# Zynq_config_JTAG_Debug.net
KiCad netlist of a schematic drawn in Altium Designer
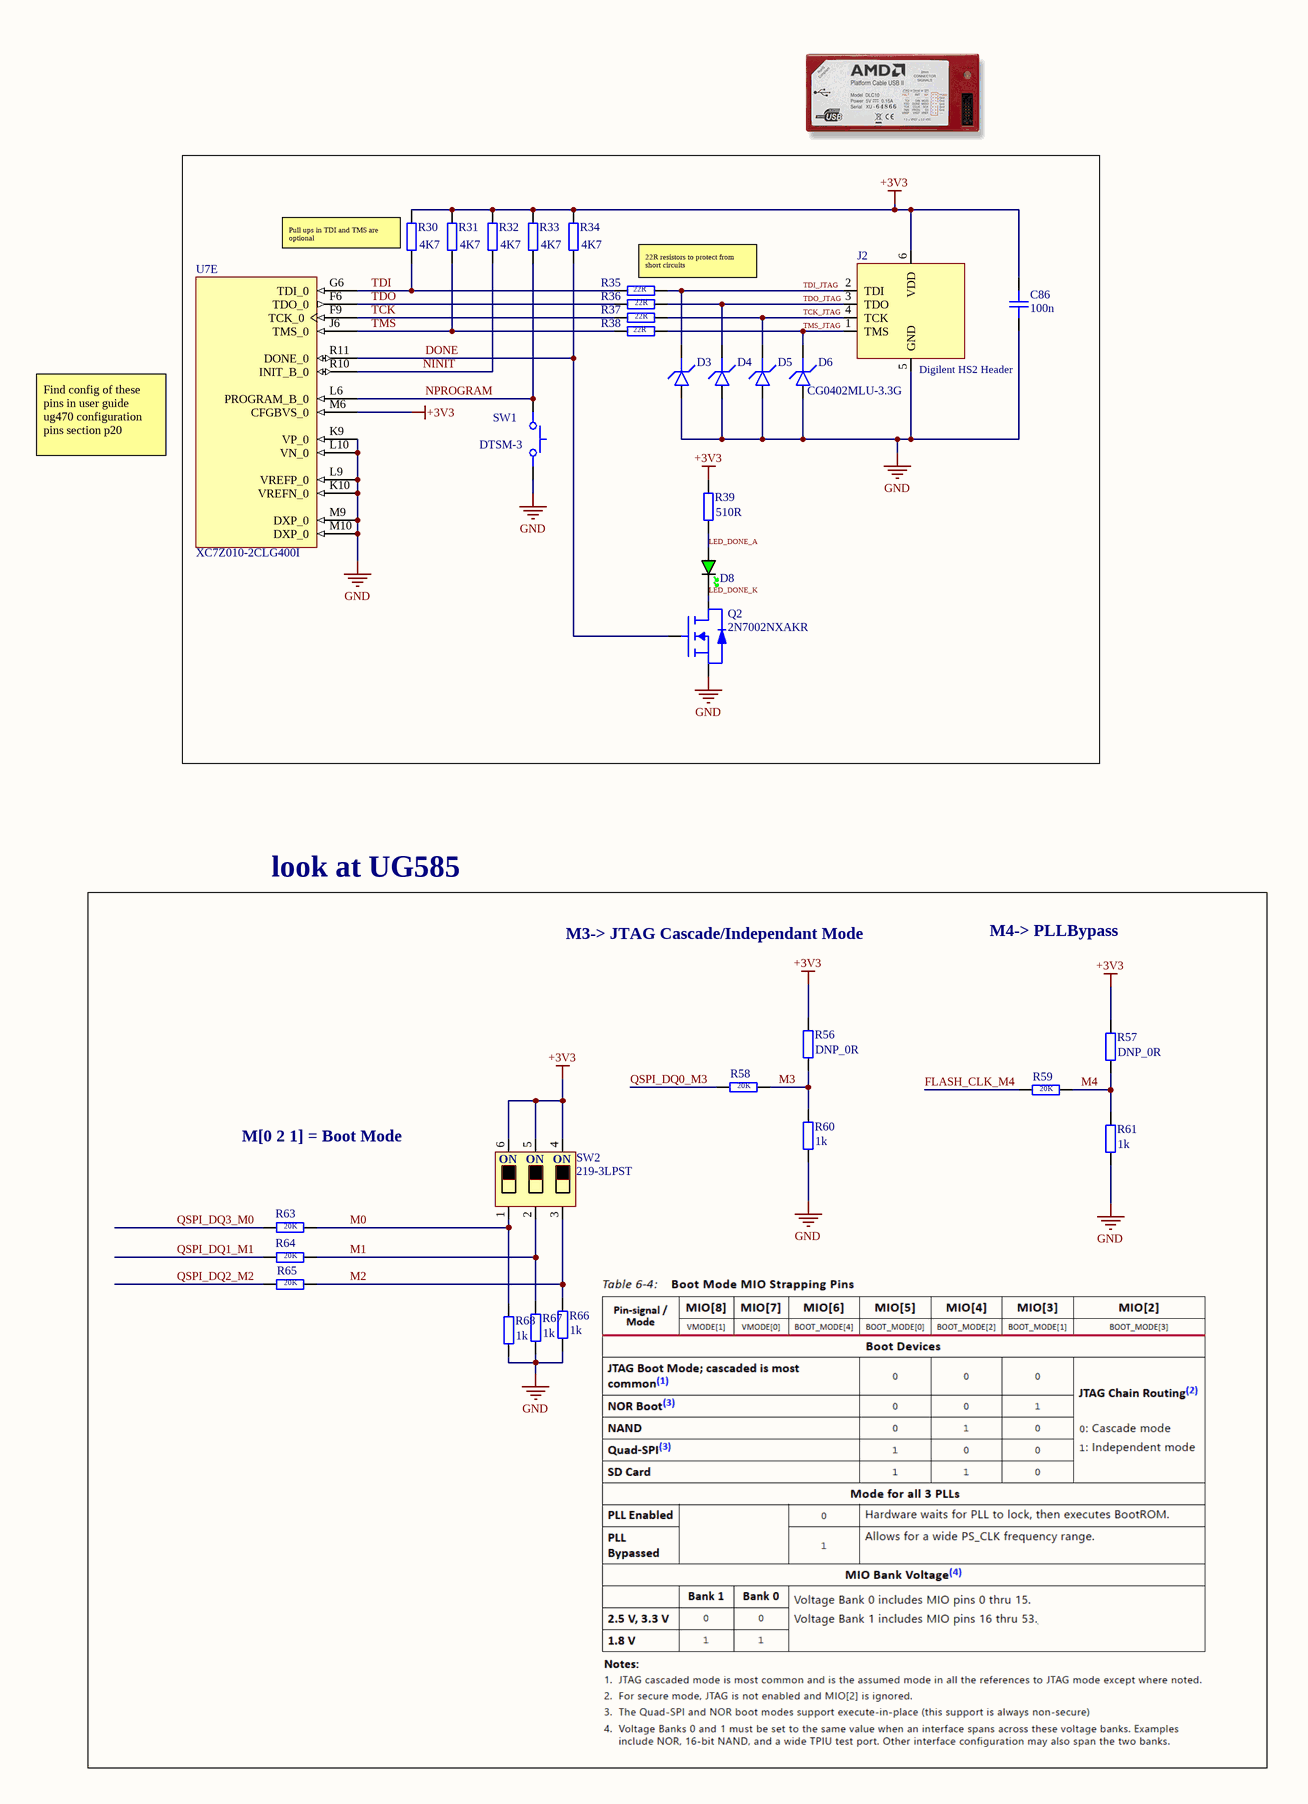
[diagram p0: Zynq config, JTAG, Debug.SchDoc, left]
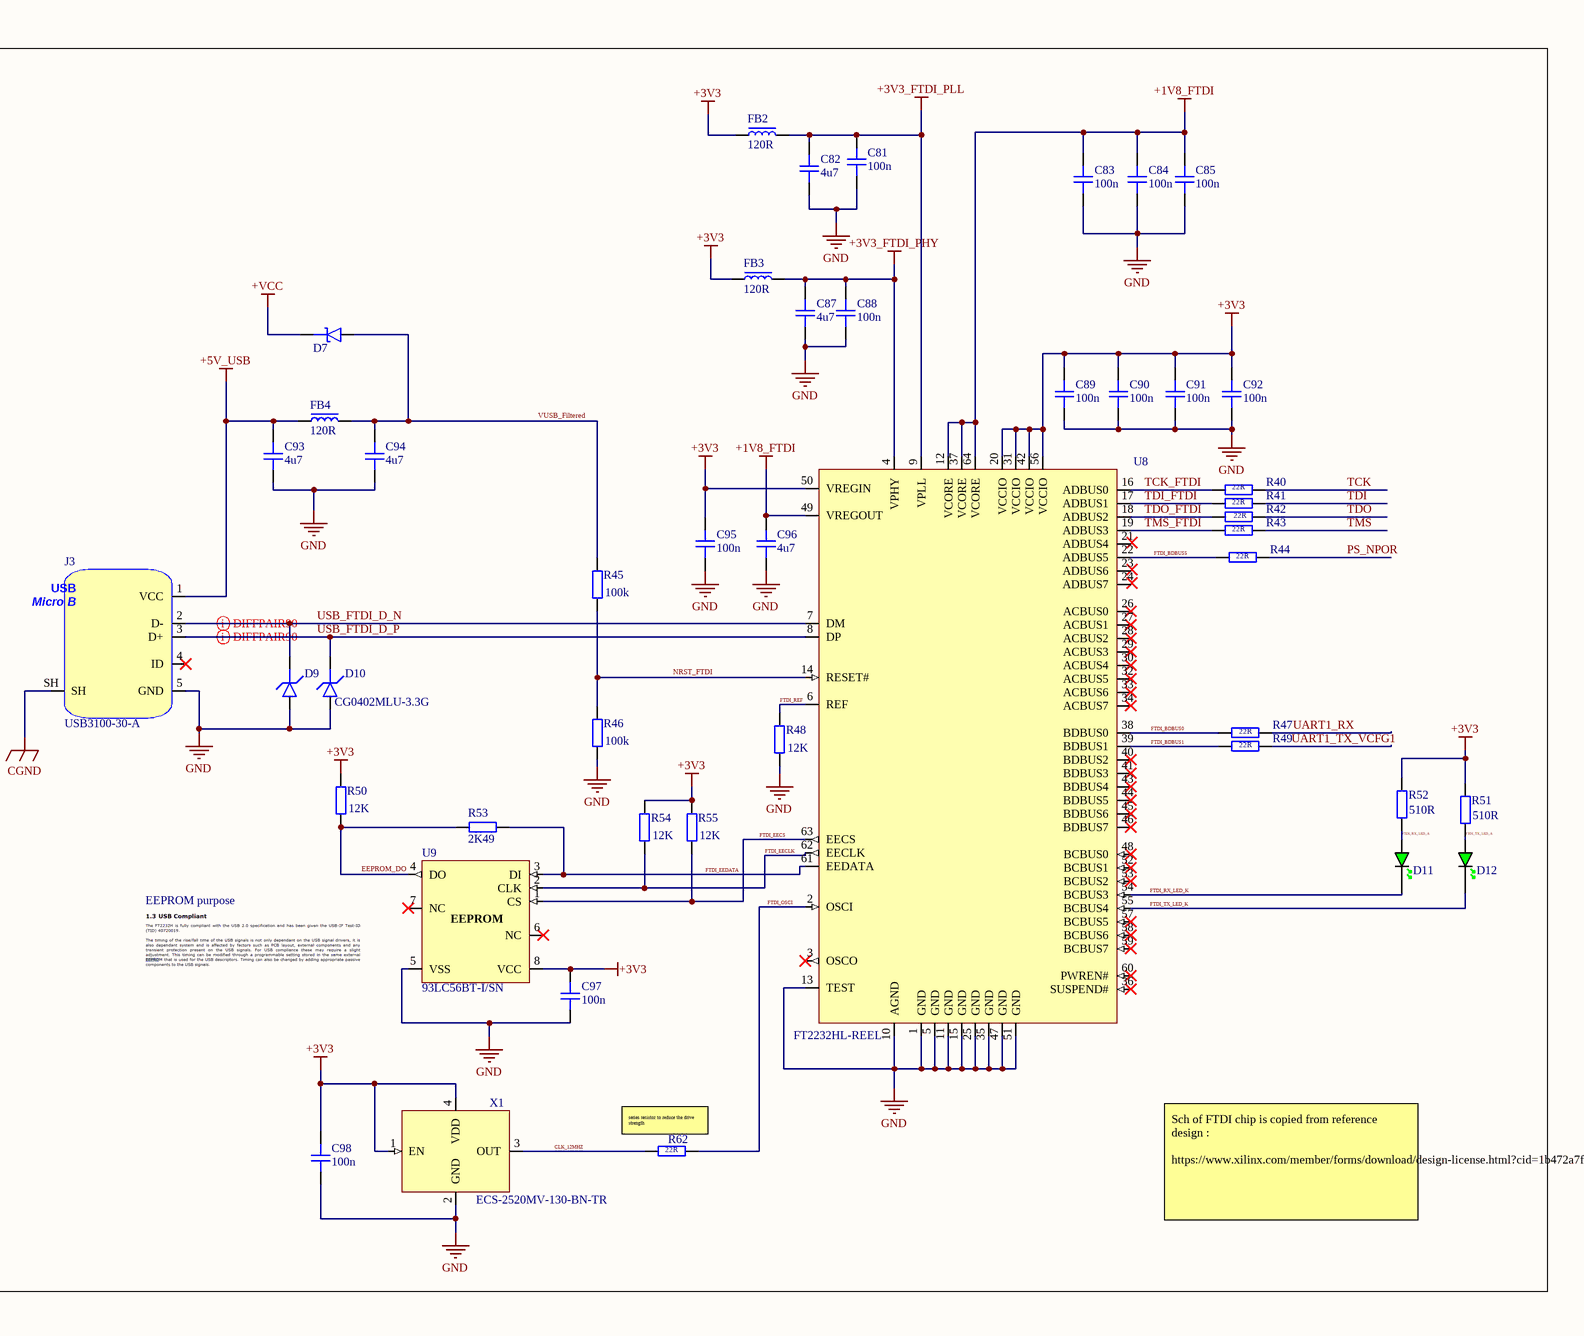
[diagram p1: Zynq config, JTAG, Debug.SchDoc, right]

(export (version "E")
  (design (tool "Eeschema 10.0.6"))
  (components
    (comp (ref "C81")
      (value "100n")
      (footprint "CAP_0402")
      (description "Capacitor SMD 0402")
      (libsource (lib "Schematic-Lib-PhilsLab") (part "CAP_0402"))
    )
    (comp (ref "C82")
      (value "4u7")
      (footprint "CAP_0402")
      (description "Capacitor SMD 0402")
      (libsource (lib "Schematic-Lib-PhilsLab") (part "CAP_0402"))
    )
    (comp (ref "C83")
      (value "100n")
      (footprint "CAP_0402")
      (description "Capacitor SMD 0402")
      (libsource (lib "Schematic-Lib-PhilsLab") (part "CAP_0402"))
    )
    (comp (ref "C84")
      (value "100n")
      (footprint "CAP_0402")
      (description "Capacitor SMD 0402")
      (libsource (lib "Schematic-Lib-PhilsLab") (part "CAP_0402"))
    )
    (comp (ref "C85")
      (value "100n")
      (footprint "CAP_0402")
      (description "Capacitor SMD 0402")
      (libsource (lib "Schematic-Lib-PhilsLab") (part "CAP_0402"))
    )
    (comp (ref "C86")
      (value "100n")
      (footprint "CAP_0402")
      (description "Capacitor SMD 0402")
      (libsource (lib "Schematic-Lib-PhilsLab") (part "CAP_0402"))
    )
    (comp (ref "C87")
      (value "4u7")
      (footprint "CAP_0402")
      (description "Capacitor SMD 0402")
      (libsource (lib "Schematic-Lib-PhilsLab") (part "CAP_0402"))
    )
    (comp (ref "C88")
      (value "100n")
      (footprint "CAP_0402")
      (description "Capacitor SMD 0402")
      (libsource (lib "Schematic-Lib-PhilsLab") (part "CAP_0402"))
    )
    (comp (ref "C89")
      (value "100n")
      (footprint "CAP_0402")
      (description "Capacitor SMD 0402")
      (libsource (lib "Schematic-Lib-PhilsLab") (part "CAP_0402"))
    )
    (comp (ref "C90")
      (value "100n")
      (footprint "CAP_0402")
      (description "Capacitor SMD 0402")
      (libsource (lib "Schematic-Lib-PhilsLab") (part "CAP_0402"))
    )
    (comp (ref "C91")
      (value "100n")
      (footprint "CAP_0402")
      (description "Capacitor SMD 0402")
      (libsource (lib "Schematic-Lib-PhilsLab") (part "CAP_0402"))
    )
    (comp (ref "C92")
      (value "100n")
      (footprint "CAP_0402")
      (description "Capacitor SMD 0402")
      (libsource (lib "Schematic-Lib-PhilsLab") (part "CAP_0402"))
    )
    (comp (ref "C93")
      (value "4u7")
      (footprint "CAP_0402")
      (description "Capacitor SMD 0402")
      (libsource (lib "Schematic-Lib-PhilsLab") (part "CAP_0402"))
    )
    (comp (ref "C94")
      (value "4u7")
      (footprint "CAP_0402")
      (description "Capacitor SMD 0402")
      (libsource (lib "Schematic-Lib-PhilsLab") (part "CAP_0402"))
    )
    (comp (ref "C95")
      (value "100n")
      (footprint "CAP_0402")
      (description "Capacitor SMD 0402")
      (libsource (lib "Schematic-Lib-PhilsLab") (part "CAP_0402"))
    )
    (comp (ref "C96")
      (value "4u7")
      (footprint "CAP_0402")
      (description "Capacitor SMD 0402")
      (libsource (lib "Schematic-Lib-PhilsLab") (part "CAP_0402"))
    )
    (comp (ref "C97")
      (value "100n")
      (footprint "CAP_0402")
      (description "Capacitor SMD 0402")
      (libsource (lib "Schematic-Lib-PhilsLab") (part "CAP_0402"))
    )
    (comp (ref "C98")
      (value "100n")
      (footprint "CAP_0402")
      (description "Capacitor SMD 0402")
      (libsource (lib "Schematic-Lib-PhilsLab") (part "CAP_0402"))
    )
    (comp (ref "D3")
      (value "D_TVS_0402")
      (footprint "D_0402")
      (description "Diode TVS / ESD 0402")
      (libsource (lib "Schematic-Lib-PhilsLab") (part "D_TVS_0402"))
    )
    (comp (ref "D4")
      (value "D_TVS_0402")
      (footprint "D_0402")
      (description "Diode TVS / ESD 0402")
      (libsource (lib "Schematic-Lib-PhilsLab") (part "D_TVS_0402"))
    )
    (comp (ref "D5")
      (value "D_TVS_0402")
      (footprint "D_0402")
      (description "Diode TVS / ESD 0402")
      (libsource (lib "Schematic-Lib-PhilsLab") (part "D_TVS_0402"))
    )
    (comp (ref "D6")
      (value "D_TVS_0402")
      (footprint "D_0402")
      (description "Diode TVS / ESD 0402")
      (fields (field (name "DESIGNATOR") "CG0402MLU-3.3G"))
      (libsource (lib "Schematic-Lib-PhilsLab") (part "D_TVS_0402"))
    )
    (comp (ref "D7")
      (value "D_SCHOTTKY_SOD_323")
      (footprint "SOD-323")
      (description "Diode Schottky SMD SOD-323")
      (libsource (lib "Schematic-Lib-PhilsLab") (part "D_SCHOTTKY_SOD_323"))
    )
    (comp (ref "D8")
      (value "GREEN")
      (footprint "LED_0402_GREEN")
      (description "LED 0402 GREEN SMD")
      (libsource (lib "Schematic-Lib-PhilsLab") (part "LED_0402_GREEN"))
    )
    (comp (ref "D9")
      (value "D_TVS_0402")
      (footprint "D_0402")
      (description "Diode TVS / ESD 0402")
      (libsource (lib "Schematic-Lib-PhilsLab") (part "D_TVS_0402"))
    )
    (comp (ref "D10")
      (value "D_TVS_0402")
      (footprint "D_0402")
      (description "Diode TVS / ESD 0402")
      (fields (field (name "DESIGNATOR") "CG0402MLU-3.3G"))
      (libsource (lib "Schematic-Lib-PhilsLab") (part "D_TVS_0402"))
    )
    (comp (ref "D11")
      (value "GREEN")
      (footprint "LED_0402_GREEN")
      (description "LED 0402 GREEN SMD")
      (libsource (lib "Schematic-Lib-PhilsLab") (part "LED_0402_GREEN"))
    )
    (comp (ref "D12")
      (value "GREEN")
      (footprint "LED_0402_GREEN")
      (description "LED 0402 GREEN SMD")
      (libsource (lib "Schematic-Lib-PhilsLab") (part "LED_0402_GREEN"))
    )
    (comp (ref "FB2")
      (value "120R")
      (footprint "FB_0402")
      (description "Ferrite Bead SMD 0402")
      (libsource (lib "Schematic-Lib-PhilsLab") (part "FB_0402"))
    )
    (comp (ref "FB3")
      (value "120R")
      (footprint "FB_0402")
      (description "Ferrite Bead SMD 0402")
      (libsource (lib "Schematic-Lib-PhilsLab") (part "FB_0402"))
    )
    (comp (ref "FB4")
      (value "120R")
      (footprint "FB_0402")
      (description "Ferrite Bead SMD 0402")
      (libsource (lib "Schematic-Lib-PhilsLab") (part "FB_0402"))
    )
    (comp (ref "J2")
      (value "Digilent HS2 Header")
      (footprint "DIGILENT_HS2")
      (description "Digilent HS2 6-Pin 2.54mm Pitch Header")
      (fields
        (field (name "MANUFACTURER") "Amphenol FCI")
        (field (name "MANUFACTURER PART NUMBER") "68000-406HLF")
      )
      (libsource (lib "Schematic-Lib-PhilsLab") (part "Digilent_HS2_Header"))
    )
    (comp (ref "J3")
      (value "USB3100-30-A")
      (footprint "USB3100-30-A")
      (description "USB Connector Type Micro B 2.0 SMD Reverse Mount")
      (fields (field (name "MANUFACTURER") "GCT"))
      (libsource (lib "Schematic-Lib-PhilsLab") (part "USB3100-30-A"))
    )
    (comp (ref "Q2")
      (value "2N7002NXAKR")
      (footprint "SSM3J338R,LF-SOT23-F")
      (description "MOSFET N-Channel Vds=60V Id=300mA with ESD Protection")
      (fields (field (name "MANUFACTURER") "Nexperia"))
      (libsource (lib "Schematic-Lib-PhilsLab") (part "2N7002NXAKR"))
    )
    (comp (ref "R30")
      (value "4K7")
      (footprint "RES_0402")
      (description "Resistor SMD 0402")
      (fields (field (name "Comment") "R0402"))
      (libsource (lib "Schematic-Lib-PhilsLab") (part "RES_0402"))
    )
    (comp (ref "R31")
      (value "4K7")
      (footprint "RES_0402")
      (description "Resistor SMD 0402")
      (fields (field (name "Comment") "R0402"))
      (libsource (lib "Schematic-Lib-PhilsLab") (part "RES_0402"))
    )
    (comp (ref "R32")
      (value "4K7")
      (footprint "RES_0402")
      (description "Resistor SMD 0402")
      (fields (field (name "Comment") "R0402"))
      (libsource (lib "Schematic-Lib-PhilsLab") (part "RES_0402"))
    )
    (comp (ref "R33")
      (value "4K7")
      (footprint "RES_0402")
      (description "Resistor SMD 0402")
      (fields (field (name "Comment") "R0402"))
      (libsource (lib "Schematic-Lib-PhilsLab") (part "RES_0402"))
    )
    (comp (ref "R34")
      (value "4K7")
      (footprint "RES_0402")
      (description "Resistor SMD 0402")
      (fields (field (name "Comment") "R0402"))
      (libsource (lib "Schematic-Lib-PhilsLab") (part "RES_0402"))
    )
    (comp (ref "R35")
      (value "22R")
      (footprint "RES_0402")
      (description "Resistor SMD 0402")
      (fields (field (name "Comment") "R0402"))
      (libsource (lib "Schematic-Lib-PhilsLab") (part "RES_0402"))
    )
    (comp (ref "R36")
      (value "22R")
      (footprint "RES_0402")
      (description "Resistor SMD 0402")
      (fields (field (name "Comment") "R0402"))
      (libsource (lib "Schematic-Lib-PhilsLab") (part "RES_0402"))
    )
    (comp (ref "R37")
      (value "22R")
      (footprint "RES_0402")
      (description "Resistor SMD 0402")
      (fields (field (name "Comment") "R0402"))
      (libsource (lib "Schematic-Lib-PhilsLab") (part "RES_0402"))
    )
    (comp (ref "R38")
      (value "22R")
      (footprint "RES_0402")
      (description "Resistor SMD 0402")
      (fields (field (name "Comment") "R0402"))
      (libsource (lib "Schematic-Lib-PhilsLab") (part "RES_0402"))
    )
    (comp (ref "R39")
      (value "510R")
      (footprint "RES_0402")
      (description "Resistor SMD 0402")
      (fields (field (name "Comment") "R0402"))
      (libsource (lib "Schematic-Lib-PhilsLab") (part "RES_0402"))
    )
    (comp (ref "R40")
      (value "22R")
      (footprint "RES_0402")
      (description "Resistor SMD 0402")
      (fields (field (name "Comment") "R0402"))
      (libsource (lib "Schematic-Lib-PhilsLab") (part "RES_0402"))
    )
    (comp (ref "R41")
      (value "22R")
      (footprint "RES_0402")
      (description "Resistor SMD 0402")
      (fields (field (name "Comment") "R0402"))
      (libsource (lib "Schematic-Lib-PhilsLab") (part "RES_0402"))
    )
    (comp (ref "R42")
      (value "22R")
      (footprint "RES_0402")
      (description "Resistor SMD 0402")
      (fields (field (name "Comment") "R0402"))
      (libsource (lib "Schematic-Lib-PhilsLab") (part "RES_0402"))
    )
    (comp (ref "R43")
      (value "22R")
      (footprint "RES_0402")
      (description "Resistor SMD 0402")
      (fields (field (name "Comment") "R0402"))
      (libsource (lib "Schematic-Lib-PhilsLab") (part "RES_0402"))
    )
    (comp (ref "R44")
      (value "22R")
      (footprint "RES_0402")
      (description "Resistor SMD 0402")
      (fields (field (name "Comment") "R0402"))
      (libsource (lib "Schematic-Lib-PhilsLab") (part "RES_0402"))
    )
    (comp (ref "R45")
      (value "100k")
      (footprint "RES_0402")
      (description "Resistor SMD 0402")
      (fields (field (name "Comment") "R0402"))
      (libsource (lib "Schematic-Lib-PhilsLab") (part "RES_0402"))
    )
    (comp (ref "R46")
      (value "100k")
      (footprint "RES_0402")
      (description "Resistor SMD 0402")
      (fields (field (name "Comment") "R0402"))
      (libsource (lib "Schematic-Lib-PhilsLab") (part "RES_0402"))
    )
    (comp (ref "R47")
      (value "22R")
      (footprint "RES_0402")
      (description "Resistor SMD 0402")
      (fields (field (name "Comment") "R0402"))
      (libsource (lib "Schematic-Lib-PhilsLab") (part "RES_0402"))
    )
    (comp (ref "R48")
      (value "12K")
      (footprint "RES_0402")
      (description "Resistor SMD 0402")
      (fields (field (name "Comment") "R0402"))
      (libsource (lib "Schematic-Lib-PhilsLab") (part "RES_0402"))
    )
    (comp (ref "R49")
      (value "22R")
      (footprint "RES_0402")
      (description "Resistor SMD 0402")
      (fields (field (name "Comment") "R0402"))
      (libsource (lib "Schematic-Lib-PhilsLab") (part "RES_0402"))
    )
    (comp (ref "R50")
      (value "12K")
      (footprint "RES_0402")
      (description "Resistor SMD 0402")
      (fields (field (name "Comment") "R0402"))
      (libsource (lib "Schematic-Lib-PhilsLab") (part "RES_0402"))
    )
    (comp (ref "R51")
      (value "510R")
      (footprint "RES_0402")
      (description "Resistor SMD 0402")
      (fields (field (name "Comment") "R0402"))
      (libsource (lib "Schematic-Lib-PhilsLab") (part "RES_0402"))
    )
    (comp (ref "R52")
      (value "510R")
      (footprint "RES_0402")
      (description "Resistor SMD 0402")
      (fields (field (name "Comment") "R0402"))
      (libsource (lib "Schematic-Lib-PhilsLab") (part "RES_0402"))
    )
    (comp (ref "R53")
      (value "2K49")
      (footprint "RES_0402")
      (description "Resistor SMD 0402")
      (fields (field (name "Comment") "R0402"))
      (libsource (lib "Schematic-Lib-PhilsLab") (part "RES_0402"))
    )
    (comp (ref "R54")
      (value "12K")
      (footprint "RES_0402")
      (description "Resistor SMD 0402")
      (fields (field (name "Comment") "R0402"))
      (libsource (lib "Schematic-Lib-PhilsLab") (part "RES_0402"))
    )
    (comp (ref "R55")
      (value "12K")
      (footprint "RES_0402")
      (description "Resistor SMD 0402")
      (fields (field (name "Comment") "R0402"))
      (libsource (lib "Schematic-Lib-PhilsLab") (part "RES_0402"))
    )
    (comp (ref "R56")
      (value "DNP_0R")
      (footprint "RES_0402")
      (description "Resistor SMD 0402")
      (fields (field (name "Comment") "R0402"))
      (libsource (lib "Schematic-Lib-PhilsLab") (part "RES_0402"))
    )
    (comp (ref "R57")
      (value "DNP_0R")
      (footprint "RES_0402")
      (description "Resistor SMD 0402")
      (fields (field (name "Comment") "R0402"))
      (libsource (lib "Schematic-Lib-PhilsLab") (part "RES_0402"))
    )
    (comp (ref "R58")
      (value "20K")
      (footprint "RES_0402")
      (description "Resistor SMD 0402")
      (fields (field (name "Comment") "R0402"))
      (libsource (lib "Schematic-Lib-PhilsLab") (part "RES_0402"))
    )
    (comp (ref "R59")
      (value "20K")
      (footprint "RES_0402")
      (description "Resistor SMD 0402")
      (fields (field (name "Comment") "R0402"))
      (libsource (lib "Schematic-Lib-PhilsLab") (part "RES_0402"))
    )
    (comp (ref "R60")
      (value "1k")
      (footprint "RES_0402")
      (description "Resistor SMD 0402")
      (fields (field (name "Comment") "R0402"))
      (libsource (lib "Schematic-Lib-PhilsLab") (part "RES_0402"))
    )
    (comp (ref "R61")
      (value "1k")
      (footprint "RES_0402")
      (description "Resistor SMD 0402")
      (fields (field (name "Comment") "R0402"))
      (libsource (lib "Schematic-Lib-PhilsLab") (part "RES_0402"))
    )
    (comp (ref "R62")
      (value "22R")
      (footprint "RES_0402")
      (description "Resistor SMD 0402")
      (fields (field (name "Comment") "R0402"))
      (libsource (lib "Schematic-Lib-PhilsLab") (part "RES_0402"))
    )
    (comp (ref "R63")
      (value "20K")
      (footprint "RES_0402")
      (description "Resistor SMD 0402")
      (fields (field (name "Comment") "R0402"))
      (libsource (lib "Schematic-Lib-PhilsLab") (part "RES_0402"))
    )
    (comp (ref "R64")
      (value "20K")
      (footprint "RES_0402")
      (description "Resistor SMD 0402")
      (fields (field (name "Comment") "R0402"))
      (libsource (lib "Schematic-Lib-PhilsLab") (part "RES_0402"))
    )
    (comp (ref "R65")
      (value "20K")
      (footprint "RES_0402")
      (description "Resistor SMD 0402")
      (fields (field (name "Comment") "R0402"))
      (libsource (lib "Schematic-Lib-PhilsLab") (part "RES_0402"))
    )
    (comp (ref "R66")
      (value "1k")
      (footprint "RES_0402")
      (description "Resistor SMD 0402")
      (fields (field (name "Comment") "R0402"))
      (libsource (lib "Schematic-Lib-PhilsLab") (part "RES_0402"))
    )
    (comp (ref "R67")
      (value "1k")
      (footprint "RES_0402")
      (description "Resistor SMD 0402")
      (fields (field (name "Comment") "R0402"))
      (libsource (lib "Schematic-Lib-PhilsLab") (part "RES_0402"))
    )
    (comp (ref "R68")
      (value "1k")
      (footprint "RES_0402")
      (description "Resistor SMD 0402")
      (fields (field (name "Comment") "R0402"))
      (libsource (lib "Schematic-Lib-PhilsLab") (part "RES_0402"))
    )
    (comp (ref "SW1")
      (value "DTSM-3")
      (footprint "DTSM-3")
      (description "Tactile Switch SMD SPST")
      (fields (field (name "MANUFACTURER") "Diptronics"))
      (libsource (lib "Schematic-Lib-PhilsLab") (part "DTSM-3"))
    )
    (comp (ref "SW2")
      (value "219-3LPST")
      (footprint "219-3LPST")
      (description "DIP Switches SPST 3x")
      (fields (field (name "MANUFACTURER") "CTS"))
      (libsource (lib "Schematic-Lib-PhilsLab") (part "219-3LPST"))
    )
    (comp (ref "U7")
      (value "XC7Z010-2CLG400I")
      (footprint "BGA400C80P20X20_1700X1700X160N")
      (libsource (lib "Zynq_SOM") (part "XC7Z010-2CLG400I"))
    )
    (comp (ref "U8")
      (value "FT2232HL-REEL")
      (footprint "LQFP-64-0.5mm")
      (description "Hi-Speed Dual USB UART/FIFO IC")
      (fields (field (name "MANUFACTURER") "FTDI"))
      (libsource (lib "Schematic-Lib-PhilsLab") (part "FT2232HL-REEL"))
    )
    (comp (ref "U9")
      (value "93LC56BT-I/SN")
      (footprint "SOIC-8")
      (description "2K Microwire Compatible Serial EEPROM")
      (fields (field (name "MANUFACTURER") "Microchip"))
      (libsource (lib "Schematic-Lib-PhilsLab") (part "93LC56BT-I/SN"))
    )
    (comp (ref "X1")
      (value "ECS-2520MV-130-BN-TR")
      (footprint "XTAL_2520")
      (fields (field (name "MANUFACTURER") "ECS"))
      (libsource (lib "Schematic-Lib-PhilsLab") (part "ECS-2520MV-130-BN-TR"))
    )
  )
  (nets
    (net (code "1") (name "+1V8_FTDI") (class "Default")
      (node (ref "C83") (pin "2") (pinfunction "2_2") (pintype "passive"))
      (node (ref "C84") (pin "2") (pinfunction "2_2") (pintype "passive"))
      (node (ref "C85") (pin "2") (pinfunction "2_2") (pintype "passive"))
      (node (ref "C96") (pin "2") (pinfunction "2_2") (pintype "passive"))
      (node (ref "U8") (pin "12") (pinfunction "VCORE_12") (pintype "power_in"))
      (node (ref "U8") (pin "37") (pinfunction "VCORE_37") (pintype "power_in"))
      (node (ref "U8") (pin "49") (pinfunction "VREGOUT_49") (pintype "power_in"))
      (node (ref "U8") (pin "64") (pinfunction "VCORE_64") (pintype "power_in"))
    )
    (net (code "2") (name "+3V3") (class "Default")
      (node (ref "C86") (pin "2") (pinfunction "2_2") (pintype "passive"))
      (node (ref "C89") (pin "2") (pinfunction "2_2") (pintype "passive"))
      (node (ref "C90") (pin "2") (pinfunction "2_2") (pintype "passive"))
      (node (ref "C91") (pin "2") (pinfunction "2_2") (pintype "passive"))
      (node (ref "C92") (pin "2") (pinfunction "2_2") (pintype "passive"))
      (node (ref "C95") (pin "2") (pinfunction "2_2") (pintype "passive"))
      (node (ref "C97") (pin "2") (pinfunction "2_2") (pintype "passive"))
      (node (ref "C98") (pin "2") (pinfunction "2_2") (pintype "passive"))
      (node (ref "FB2") (pin "1") (pinfunction "1_1") (pintype "passive"))
      (node (ref "FB3") (pin "1") (pinfunction "1_1") (pintype "passive"))
      (node (ref "J2") (pin "6") (pinfunction "VDD_6") (pintype "power_in"))
      (node (ref "R30") (pin "2") (pinfunction "2_2") (pintype "passive"))
      (node (ref "R31") (pin "2") (pinfunction "2_2") (pintype "passive"))
      (node (ref "R32") (pin "2") (pinfunction "2_2") (pintype "passive"))
      (node (ref "R33") (pin "2") (pinfunction "2_2") (pintype "passive"))
      (node (ref "R34") (pin "2") (pinfunction "2_2") (pintype "passive"))
      (node (ref "R39") (pin "1") (pinfunction "1_1") (pintype "passive"))
      (node (ref "R50") (pin "2") (pinfunction "2_2") (pintype "passive"))
      (node (ref "R51") (pin "1") (pinfunction "1_1") (pintype "passive"))
      (node (ref "R52") (pin "1") (pinfunction "1_1") (pintype "passive"))
      (node (ref "R54") (pin "2") (pinfunction "2_2") (pintype "passive"))
      (node (ref "R55") (pin "2") (pinfunction "2_2") (pintype "passive"))
      (node (ref "R56") (pin "1") (pinfunction "1_1") (pintype "passive"))
      (node (ref "R57") (pin "1") (pinfunction "1_1") (pintype "passive"))
      (node (ref "SW2") (pin "4") (pinfunction "4_4") (pintype "passive"))
      (node (ref "SW2") (pin "5") (pinfunction "5_5") (pintype "passive"))
      (node (ref "SW2") (pin "6") (pinfunction "6_6") (pintype "passive"))
      (node (ref "U7") (pin "M6") (pinfunction "CFGBVS_0_M6") (pintype "input"))
      (node (ref "U8") (pin "20") (pinfunction "VCCIO_20") (pintype "power_in"))
      (node (ref "U8") (pin "31") (pinfunction "VCCIO_31") (pintype "power_in"))
      (node (ref "U8") (pin "42") (pinfunction "VCCIO_42") (pintype "power_in"))
      (node (ref "U8") (pin "50") (pinfunction "VREGIN_50") (pintype "power_in"))
      (node (ref "U8") (pin "56") (pinfunction "VCCIO_56") (pintype "power_in"))
      (node (ref "U9") (pin "8") (pinfunction "VCC_8") (pintype "power_in"))
      (node (ref "X1") (pin "1") (pinfunction "EN_1") (pintype "input"))
      (node (ref "X1") (pin "4") (pinfunction "VDD_4") (pintype "power_in"))
    )
    (net (code "3") (name "+3V3_FTDI_PHY") (class "Default")
      (node (ref "C87") (pin "2") (pinfunction "2_2") (pintype "passive"))
      (node (ref "C88") (pin "2") (pinfunction "2_2") (pintype "passive"))
      (node (ref "FB3") (pin "2") (pinfunction "2_2") (pintype "passive"))
      (node (ref "U8") (pin "4") (pinfunction "VPHY_4") (pintype "power_in"))
    )
    (net (code "4") (name "+3V3_FTDI_PLL") (class "Default")
      (node (ref "C81") (pin "2") (pinfunction "2_2") (pintype "passive"))
      (node (ref "C82") (pin "2") (pinfunction "2_2") (pintype "passive"))
      (node (ref "FB2") (pin "2") (pinfunction "2_2") (pintype "passive"))
      (node (ref "U8") (pin "9") (pinfunction "VPLL_9") (pintype "power_in"))
    )
    (net (code "5") (name "+5V_USB") (class "Default")
      (node (ref "C93") (pin "2") (pinfunction "2_2") (pintype "passive"))
      (node (ref "FB4") (pin "1") (pinfunction "1_1") (pintype "passive"))
      (node (ref "J3") (pin "1") (pinfunction "VCC_1") (pintype "passive"))
    )
    (net (code "6") (name "+VCC") (class "Default")
      (node (ref "D7") (pin "K") (pinfunction "K_K") (pintype "passive"))
    )
    (net (code "7") (name "/CLK_12MHZ") (class "Default")
      (node (ref "R62") (pin "1") (pinfunction "1_1") (pintype "passive"))
      (node (ref "X1") (pin "3") (pinfunction "OUT_3") (pintype "passive"))
    )
    (net (code "8") (name "/DONE") (class "Default")
      (node (ref "Q2") (pin "G") (pinfunction "G_G") (pintype "passive"))
      (node (ref "R34") (pin "1") (pinfunction "1_1") (pintype "passive"))
      (node (ref "U7") (pin "R11") (pinfunction "DONE_0_R11") (pintype "bidirectional"))
    )
    (net (code "9") (name "/EEPROM_DO") (class "Default")
      (node (ref "R50") (pin "1") (pinfunction "1_1") (pintype "passive"))
      (node (ref "R53") (pin "2") (pinfunction "2_2") (pintype "passive"))
      (node (ref "U9") (pin "4") (pinfunction "DO_4") (pintype "output"))
    )
    (net (code "10") (name "/FLASH_CLK_M4") (class "Default")
      (node (ref "R59") (pin "1") (pinfunction "1_1") (pintype "passive"))
    )
    (net (code "11") (name "/FTDI_BDBUS0") (class "Default")
      (node (ref "R47") (pin "1") (pinfunction "1_1") (pintype "passive"))
      (node (ref "U8") (pin "38") (pinfunction "BDBUS0_38") (pintype "bidirectional"))
    )
    (net (code "12") (name "/FTDI_BDBUS1") (class "Default")
      (node (ref "R49") (pin "1") (pinfunction "1_1") (pintype "passive"))
      (node (ref "U8") (pin "39") (pinfunction "BDBUS1_39") (pintype "bidirectional"))
    )
    (net (code "13") (name "/FTDI_BDBUS5") (class "Default")
      (node (ref "R44") (pin "1") (pinfunction "1_1") (pintype "passive"))
      (node (ref "U8") (pin "22") (pinfunction "ADBUS5_22") (pintype "bidirectional"))
    )
    (net (code "14") (name "/FTDI_EECLK") (class "Default")
      (node (ref "R54") (pin "1") (pinfunction "1_1") (pintype "passive"))
      (node (ref "U8") (pin "62") (pinfunction "EECLK_62") (pintype "output"))
      (node (ref "U9") (pin "2") (pinfunction "CLK_2") (pintype "input"))
    )
    (net (code "15") (name "/FTDI_EECS") (class "Default")
      (node (ref "R55") (pin "1") (pinfunction "1_1") (pintype "passive"))
      (node (ref "U8") (pin "63") (pinfunction "EECS_63") (pintype "output"))
      (node (ref "U9") (pin "1") (pinfunction "CS_1") (pintype "input"))
    )
    (net (code "16") (name "/FTDI_EEDATA") (class "Default")
      (node (ref "R53") (pin "1") (pinfunction "1_1") (pintype "passive"))
      (node (ref "U8") (pin "61") (pinfunction "EEDATA_61") (pintype "bidirectional"))
      (node (ref "U9") (pin "3") (pinfunction "DI_3") (pintype "input"))
    )
    (net (code "17") (name "/FTDI_OSCI") (class "Default")
      (node (ref "R62") (pin "2") (pinfunction "2_2") (pintype "passive"))
      (node (ref "U8") (pin "2") (pinfunction "OSCI_2") (pintype "input"))
    )
    (net (code "18") (name "/FTDI_REF") (class "Default")
      (node (ref "R48") (pin "2") (pinfunction "2_2") (pintype "passive"))
      (node (ref "U8") (pin "6") (pinfunction "REF_6") (pintype "passive"))
    )
    (net (code "19") (name "/FTDI_RX_LED_A") (class "Default")
      (node (ref "D11") (pin "A") (pinfunction "A_A") (pintype "passive"))
      (node (ref "R52") (pin "2") (pinfunction "2_2") (pintype "passive"))
    )
    (net (code "20") (name "/FTDI_RX_LED_K") (class "Default")
      (node (ref "D11") (pin "K") (pinfunction "K_K") (pintype "passive"))
      (node (ref "U8") (pin "54") (pinfunction "BCBUS3_54") (pintype "input"))
    )
    (net (code "21") (name "/FTDI_TX_LED_A") (class "Default")
      (node (ref "D12") (pin "A") (pinfunction "A_A") (pintype "passive"))
      (node (ref "R51") (pin "2") (pinfunction "2_2") (pintype "passive"))
    )
    (net (code "22") (name "/FTDI_TX_LED_K") (class "Default")
      (node (ref "D12") (pin "K") (pinfunction "K_K") (pintype "passive"))
      (node (ref "U8") (pin "55") (pinfunction "BCBUS4_55") (pintype "input"))
    )
    (net (code "23") (name "/LED_DONE_A") (class "Default")
      (node (ref "D8") (pin "A") (pinfunction "A_A") (pintype "passive"))
      (node (ref "R39") (pin "2") (pinfunction "2_2") (pintype "passive"))
    )
    (net (code "24") (name "/LED_DONE_K") (class "Default")
      (node (ref "D8") (pin "K") (pinfunction "K_K") (pintype "passive"))
      (node (ref "Q2") (pin "D") (pinfunction "D_D") (pintype "passive"))
    )
    (net (code "25") (name "/M0") (class "Default")
      (node (ref "R63") (pin "2") (pinfunction "2_2") (pintype "passive"))
      (node (ref "R68") (pin "1") (pinfunction "1_1") (pintype "passive"))
      (node (ref "SW2") (pin "1") (pinfunction "1_1") (pintype "passive"))
    )
    (net (code "26") (name "/M1") (class "Default")
      (node (ref "R64") (pin "2") (pinfunction "2_2") (pintype "passive"))
      (node (ref "R67") (pin "1") (pinfunction "1_1") (pintype "passive"))
      (node (ref "SW2") (pin "2") (pinfunction "2_2") (pintype "passive"))
    )
    (net (code "27") (name "/M2") (class "Default")
      (node (ref "R65") (pin "2") (pinfunction "2_2") (pintype "passive"))
      (node (ref "R66") (pin "1") (pinfunction "1_1") (pintype "passive"))
      (node (ref "SW2") (pin "3") (pinfunction "3_3") (pintype "passive"))
    )
    (net (code "28") (name "/M3") (class "Default")
      (node (ref "R56") (pin "2") (pinfunction "2_2") (pintype "passive"))
      (node (ref "R58") (pin "2") (pinfunction "2_2") (pintype "passive"))
      (node (ref "R60") (pin "1") (pinfunction "1_1") (pintype "passive"))
    )
    (net (code "29") (name "/M4") (class "Default")
      (node (ref "R57") (pin "2") (pinfunction "2_2") (pintype "passive"))
      (node (ref "R59") (pin "2") (pinfunction "2_2") (pintype "passive"))
      (node (ref "R61") (pin "1") (pinfunction "1_1") (pintype "passive"))
    )
    (net (code "30") (name "/NINIT") (class "Default")
      (node (ref "R32") (pin "1") (pinfunction "1_1") (pintype "passive"))
      (node (ref "U7") (pin "R10") (pinfunction "INIT_B_0_R10") (pintype "bidirectional"))
    )
    (net (code "31") (name "/NPROGRAM") (class "Default")
      (node (ref "R33") (pin "1") (pinfunction "1_1") (pintype "passive"))
      (node (ref "SW1") (pin "1") (pintype "passive"))
      (node (ref "U7") (pin "L6") (pinfunction "PROGRAM_B_0_L6") (pintype "input"))
    )
    (net (code "32") (name "/NRST_FTDI") (class "Default")
      (node (ref "R45") (pin "1") (pinfunction "1_1") (pintype "passive"))
      (node (ref "R46") (pin "2") (pinfunction "2_2") (pintype "passive"))
      (node (ref "U8") (pin "14") (pinfunction "RESET#_14") (pintype "input"))
    )
    (net (code "33") (name "/PS_NPOR") (class "Default")
      (node (ref "R44") (pin "2") (pinfunction "2_2") (pintype "passive"))
    )
    (net (code "34") (name "/QSPI_DQ0_M3") (class "Default")
      (node (ref "R58") (pin "1") (pinfunction "1_1") (pintype "passive"))
    )
    (net (code "35") (name "/QSPI_DQ1_M1") (class "Default")
      (node (ref "R64") (pin "1") (pinfunction "1_1") (pintype "passive"))
    )
    (net (code "36") (name "/QSPI_DQ2_M2") (class "Default")
      (node (ref "R65") (pin "1") (pinfunction "1_1") (pintype "passive"))
    )
    (net (code "37") (name "/QSPI_DQ3_M0") (class "Default")
      (node (ref "R63") (pin "1") (pinfunction "1_1") (pintype "passive"))
    )
    (net (code "38") (name "/TCK") (class "Default")
      (node (ref "R37") (pin "2") (pinfunction "2_2") (pintype "passive"))
      (node (ref "R40") (pin "2") (pinfunction "2_2") (pintype "passive"))
      (node (ref "U7") (pin "F9") (pinfunction "TCK_0_F9") (pintype "input"))
    )
    (net (code "39") (name "/TCK_FTDI") (class "Default")
      (node (ref "R40") (pin "1") (pinfunction "1_1") (pintype "passive"))
      (node (ref "U8") (pin "16") (pinfunction "ADBUS0_16") (pintype "bidirectional"))
    )
    (net (code "40") (name "/TCK_JTAG") (class "Default")
      (node (ref "D5") (pin "K") (pinfunction "K_K") (pintype "passive"))
      (node (ref "J2") (pin "4") (pinfunction "TCK_4") (pintype "passive"))
      (node (ref "R37") (pin "1") (pinfunction "1_1") (pintype "passive"))
    )
    (net (code "41") (name "/TDI") (class "Default")
      (node (ref "R30") (pin "1") (pinfunction "1_1") (pintype "passive"))
      (node (ref "R35") (pin "2") (pinfunction "2_2") (pintype "passive"))
      (node (ref "R41") (pin "2") (pinfunction "2_2") (pintype "passive"))
      (node (ref "U7") (pin "G6") (pinfunction "TDI_0_G6") (pintype "input"))
    )
    (net (code "42") (name "/TDI_FTDI") (class "Default")
      (node (ref "R41") (pin "1") (pinfunction "1_1") (pintype "passive"))
      (node (ref "U8") (pin "17") (pinfunction "ADBUS1_17") (pintype "bidirectional"))
    )
    (net (code "43") (name "/TDI_JTAG") (class "Default")
      (node (ref "D3") (pin "K") (pinfunction "K_K") (pintype "passive"))
      (node (ref "J2") (pin "2") (pinfunction "TDI_2") (pintype "passive"))
      (node (ref "R35") (pin "1") (pinfunction "1_1") (pintype "passive"))
    )
    (net (code "44") (name "/TDO") (class "Default")
      (node (ref "R36") (pin "2") (pinfunction "2_2") (pintype "passive"))
      (node (ref "R42") (pin "2") (pinfunction "2_2") (pintype "passive"))
      (node (ref "U7") (pin "F6") (pinfunction "TDO_0_F6") (pintype "output"))
    )
    (net (code "45") (name "/TDO_FTDI") (class "Default")
      (node (ref "R42") (pin "1") (pinfunction "1_1") (pintype "passive"))
      (node (ref "U8") (pin "18") (pinfunction "ADBUS2_18") (pintype "bidirectional"))
    )
    (net (code "46") (name "/TDO_JTAG") (class "Default")
      (node (ref "D4") (pin "K") (pinfunction "K_K") (pintype "passive"))
      (node (ref "J2") (pin "3") (pinfunction "TDO_3") (pintype "passive"))
      (node (ref "R36") (pin "1") (pinfunction "1_1") (pintype "passive"))
    )
    (net (code "47") (name "/TMS") (class "Default")
      (node (ref "R31") (pin "1") (pinfunction "1_1") (pintype "passive"))
      (node (ref "R38") (pin "2") (pinfunction "2_2") (pintype "passive"))
      (node (ref "R43") (pin "2") (pinfunction "2_2") (pintype "passive"))
      (node (ref "U7") (pin "J6") (pinfunction "TMS_0_J6") (pintype "input"))
    )
    (net (code "48") (name "/TMS_FTDI") (class "Default")
      (node (ref "R43") (pin "1") (pinfunction "1_1") (pintype "passive"))
      (node (ref "U8") (pin "19") (pinfunction "ADBUS3_19") (pintype "bidirectional"))
    )
    (net (code "49") (name "/TMS_JTAG") (class "Default")
      (node (ref "D6") (pin "K") (pinfunction "K_K") (pintype "passive"))
      (node (ref "J2") (pin "1") (pinfunction "TMS_1") (pintype "passive"))
      (node (ref "R38") (pin "1") (pinfunction "1_1") (pintype "passive"))
    )
    (net (code "50") (name "/UART1_RX") (class "Default")
      (node (ref "R47") (pin "2") (pinfunction "2_2") (pintype "passive"))
    )
    (net (code "51") (name "/UART1_TX_VCFG1") (class "Default")
      (node (ref "R49") (pin "2") (pinfunction "2_2") (pintype "passive"))
    )
    (net (code "52") (name "/USB_FTDI_D_N") (class "Default")
      (node (ref "D9") (pin "K") (pinfunction "K_K") (pintype "passive"))
      (node (ref "J3") (pin "2") (pinfunction "D-_2") (pintype "passive"))
      (node (ref "U8") (pin "7") (pinfunction "DM_7") (pintype "bidirectional"))
    )
    (net (code "53") (name "/USB_FTDI_D_P") (class "Default")
      (node (ref "D10") (pin "K") (pinfunction "K_K") (pintype "passive"))
      (node (ref "J3") (pin "3") (pinfunction "D+_3") (pintype "passive"))
      (node (ref "U8") (pin "8") (pinfunction "DP_8") (pintype "bidirectional"))
    )
    (net (code "54") (name "/VUSB_Filtered") (class "Default")
      (node (ref "C94") (pin "2") (pinfunction "2_2") (pintype "passive"))
      (node (ref "D7") (pin "A") (pinfunction "A_A") (pintype "passive"))
      (node (ref "FB4") (pin "2") (pinfunction "2_2") (pintype "passive"))
      (node (ref "R45") (pin "2") (pinfunction "2_2") (pintype "passive"))
    )
    (net (code "55") (name "CGND") (class "Default")
      (node (ref "J3") (pin "SH") (pinfunction "SH_SH") (pintype "passive"))
    )
    (net (code "56") (name "GND") (class "Default")
      (node (ref "C81") (pin "1") (pinfunction "1_1") (pintype "passive"))
      (node (ref "C82") (pin "1") (pinfunction "1_1") (pintype "passive"))
      (node (ref "C83") (pin "1") (pinfunction "1_1") (pintype "passive"))
      (node (ref "C84") (pin "1") (pinfunction "1_1") (pintype "passive"))
      (node (ref "C85") (pin "1") (pinfunction "1_1") (pintype "passive"))
      (node (ref "C86") (pin "1") (pinfunction "1_1") (pintype "passive"))
      (node (ref "C87") (pin "1") (pinfunction "1_1") (pintype "passive"))
      (node (ref "C88") (pin "1") (pinfunction "1_1") (pintype "passive"))
      (node (ref "C89") (pin "1") (pinfunction "1_1") (pintype "passive"))
      (node (ref "C90") (pin "1") (pinfunction "1_1") (pintype "passive"))
      (node (ref "C91") (pin "1") (pinfunction "1_1") (pintype "passive"))
      (node (ref "C92") (pin "1") (pinfunction "1_1") (pintype "passive"))
      (node (ref "C93") (pin "1") (pinfunction "1_1") (pintype "passive"))
      (node (ref "C94") (pin "1") (pinfunction "1_1") (pintype "passive"))
      (node (ref "C95") (pin "1") (pinfunction "1_1") (pintype "passive"))
      (node (ref "C96") (pin "1") (pinfunction "1_1") (pintype "passive"))
      (node (ref "C97") (pin "1") (pinfunction "1_1") (pintype "passive"))
      (node (ref "C98") (pin "1") (pinfunction "1_1") (pintype "passive"))
      (node (ref "D10") (pin "A") (pinfunction "A_A") (pintype "passive"))
      (node (ref "D3") (pin "A") (pinfunction "A_A") (pintype "passive"))
      (node (ref "D4") (pin "A") (pinfunction "A_A") (pintype "passive"))
      (node (ref "D5") (pin "A") (pinfunction "A_A") (pintype "passive"))
      (node (ref "D6") (pin "A") (pinfunction "A_A") (pintype "passive"))
      (node (ref "D9") (pin "A") (pinfunction "A_A") (pintype "passive"))
      (node (ref "J2") (pin "5") (pinfunction "GND_5") (pintype "power_in"))
      (node (ref "J3") (pin "5") (pinfunction "GND_5") (pintype "passive"))
      (node (ref "Q2") (pin "S") (pinfunction "S_S") (pintype "passive"))
      (node (ref "R46") (pin "1") (pinfunction "1_1") (pintype "passive"))
      (node (ref "R48") (pin "1") (pinfunction "1_1") (pintype "passive"))
      (node (ref "R60") (pin "2") (pinfunction "2_2") (pintype "passive"))
      (node (ref "R61") (pin "2") (pinfunction "2_2") (pintype "passive"))
      (node (ref "R66") (pin "2") (pinfunction "2_2") (pintype "passive"))
      (node (ref "R67") (pin "2") (pinfunction "2_2") (pintype "passive"))
      (node (ref "R68") (pin "2") (pinfunction "2_2") (pintype "passive"))
      (node (ref "SW1") (pin "2") (pintype "passive"))
      (node (ref "U7") (pin "K10") (pinfunction "VREFN_0_K10") (pintype "input"))
      (node (ref "U7") (pin "K9") (pinfunction "VP_0_K9") (pintype "input"))
      (node (ref "U7") (pin "L10") (pinfunction "VN_0_L10") (pintype "input"))
      (node (ref "U7") (pin "L9") (pinfunction "VREFP_0_L9") (pintype "input"))
      (node (ref "U7") (pin "M10") (pinfunction "DXP_0_M10") (pintype "input"))
      (node (ref "U7") (pin "M9") (pinfunction "DXP_0_M9") (pintype "input"))
      (node (ref "U8") (pin "1") (pinfunction "GND_1") (pintype "power_in"))
      (node (ref "U8") (pin "10") (pinfunction "AGND_10") (pintype "power_in"))
      (node (ref "U8") (pin "11") (pinfunction "GND_11") (pintype "power_in"))
      (node (ref "U8") (pin "13") (pinfunction "TEST_13") (pintype "passive"))
      (node (ref "U8") (pin "15") (pinfunction "GND_15") (pintype "power_in"))
      (node (ref "U8") (pin "25") (pinfunction "GND_25") (pintype "power_in"))
      (node (ref "U8") (pin "35") (pinfunction "GND_35") (pintype "power_in"))
      (node (ref "U8") (pin "47") (pinfunction "GND_47") (pintype "power_in"))
      (node (ref "U8") (pin "5") (pinfunction "GND_5") (pintype "power_in"))
      (node (ref "U8") (pin "51") (pinfunction "GND_51") (pintype "power_in"))
      (node (ref "U9") (pin "5") (pinfunction "VSS_5") (pintype "power_in"))
      (node (ref "X1") (pin "2") (pinfunction "GND_2") (pintype "power_in"))
    )
    (net (code "57") (name "unconnected-(J3-ID-Pad4)") (class "Default")
      (node (ref "J3") (pin "4") (pinfunction "ID_4") (pintype "passive+no_connect"))
    )
    (net (code "58") (name "unconnected-(U8-ACBUS0-Pad26)") (class "Default")
      (node (ref "U8") (pin "26") (pinfunction "ACBUS0_26") (pintype "bidirectional+no_connect"))
    )
    (net (code "59") (name "unconnected-(U8-ACBUS1-Pad27)") (class "Default")
      (node (ref "U8") (pin "27") (pinfunction "ACBUS1_27") (pintype "bidirectional+no_connect"))
    )
    (net (code "60") (name "unconnected-(U8-ACBUS2-Pad28)") (class "Default")
      (node (ref "U8") (pin "28") (pinfunction "ACBUS2_28") (pintype "bidirectional+no_connect"))
    )
    (net (code "61") (name "unconnected-(U8-ACBUS3-Pad29)") (class "Default")
      (node (ref "U8") (pin "29") (pinfunction "ACBUS3_29") (pintype "bidirectional+no_connect"))
    )
    (net (code "62") (name "unconnected-(U8-ACBUS4-Pad30)") (class "Default")
      (node (ref "U8") (pin "30") (pinfunction "ACBUS4_30") (pintype "bidirectional+no_connect"))
    )
    (net (code "63") (name "unconnected-(U8-ACBUS5-Pad32)") (class "Default")
      (node (ref "U8") (pin "32") (pinfunction "ACBUS5_32") (pintype "bidirectional+no_connect"))
    )
    (net (code "64") (name "unconnected-(U8-ACBUS6-Pad33)") (class "Default")
      (node (ref "U8") (pin "33") (pinfunction "ACBUS6_33") (pintype "bidirectional+no_connect"))
    )
    (net (code "65") (name "unconnected-(U8-ACBUS7-Pad34)") (class "Default")
      (node (ref "U8") (pin "34") (pinfunction "ACBUS7_34") (pintype "bidirectional+no_connect"))
    )
    (net (code "66") (name "unconnected-(U8-ADBUS4-Pad21)") (class "Default")
      (node (ref "U8") (pin "21") (pinfunction "ADBUS4_21") (pintype "bidirectional"))
    )
    (net (code "67") (name "unconnected-(U8-ADBUS6-Pad23)") (class "Default")
      (node (ref "U8") (pin "23") (pinfunction "ADBUS6_23") (pintype "bidirectional"))
    )
    (net (code "68") (name "unconnected-(U8-ADBUS7-Pad24)") (class "Default")
      (node (ref "U8") (pin "24") (pinfunction "ADBUS7_24") (pintype "bidirectional"))
    )
    (net (code "69") (name "unconnected-(U8-BCBUS0-Pad48)") (class "Default")
      (node (ref "U8") (pin "48") (pinfunction "BCBUS0_48") (pintype "input+no_connect"))
    )
    (net (code "70") (name "unconnected-(U8-BCBUS1-Pad52)") (class "Default")
      (node (ref "U8") (pin "52") (pinfunction "BCBUS1_52") (pintype "input+no_connect"))
    )
    (net (code "71") (name "unconnected-(U8-BCBUS2-Pad53)") (class "Default")
      (node (ref "U8") (pin "53") (pinfunction "BCBUS2_53") (pintype "input+no_connect"))
    )
    (net (code "72") (name "unconnected-(U8-BCBUS5-Pad57)") (class "Default")
      (node (ref "U8") (pin "57") (pinfunction "BCBUS5_57") (pintype "input+no_connect"))
    )
    (net (code "73") (name "unconnected-(U8-BCBUS6-Pad58)") (class "Default")
      (node (ref "U8") (pin "58") (pinfunction "BCBUS6_58") (pintype "input+no_connect"))
    )
    (net (code "74") (name "unconnected-(U8-BCBUS7-Pad59)") (class "Default")
      (node (ref "U8") (pin "59") (pinfunction "BCBUS7_59") (pintype "input+no_connect"))
    )
    (net (code "75") (name "unconnected-(U8-BDBUS2-Pad40)") (class "Default")
      (node (ref "U8") (pin "40") (pinfunction "BDBUS2_40") (pintype "bidirectional+no_connect"))
    )
    (net (code "76") (name "unconnected-(U8-BDBUS3-Pad41)") (class "Default")
      (node (ref "U8") (pin "41") (pinfunction "BDBUS3_41") (pintype "bidirectional+no_connect"))
    )
    (net (code "77") (name "unconnected-(U8-BDBUS4-Pad43)") (class "Default")
      (node (ref "U8") (pin "43") (pinfunction "BDBUS4_43") (pintype "bidirectional+no_connect"))
    )
    (net (code "78") (name "unconnected-(U8-BDBUS5-Pad44)") (class "Default")
      (node (ref "U8") (pin "44") (pinfunction "BDBUS5_44") (pintype "bidirectional+no_connect"))
    )
    (net (code "79") (name "unconnected-(U8-BDBUS6-Pad45)") (class "Default")
      (node (ref "U8") (pin "45") (pinfunction "BDBUS6_45") (pintype "bidirectional+no_connect"))
    )
    (net (code "80") (name "unconnected-(U8-BDBUS7-Pad46)") (class "Default")
      (node (ref "U8") (pin "46") (pinfunction "BDBUS7_46") (pintype "bidirectional+no_connect"))
    )
    (net (code "81") (name "unconnected-(U8-OSCO-Pad3)") (class "Default")
      (node (ref "U8") (pin "3") (pinfunction "OSCO_3") (pintype "output+no_connect"))
    )
    (net (code "82") (name "unconnected-(U8-PWREN#-Pad60)") (class "Default")
      (node (ref "U8") (pin "60") (pinfunction "PWREN#_60") (pintype "input+no_connect"))
    )
    (net (code "83") (name "unconnected-(U8-SUSPEND#-Pad36)") (class "Default")
      (node (ref "U8") (pin "36") (pinfunction "SUSPEND#_36") (pintype "input+no_connect"))
    )
    (net (code "84") (name "unconnected-(U9-NC-Pad6)") (class "Default")
      (node (ref "U9") (pin "6") (pinfunction "NC_6") (pintype "passive+no_connect"))
    )
    (net (code "85") (name "unconnected-(U9-NC-Pad7)") (class "Default")
      (node (ref "U9") (pin "7") (pinfunction "NC_7") (pintype "passive+no_connect"))
    )
  )
)
